# echo.net
KiCad netlist of a schematic drawn in EAGLE
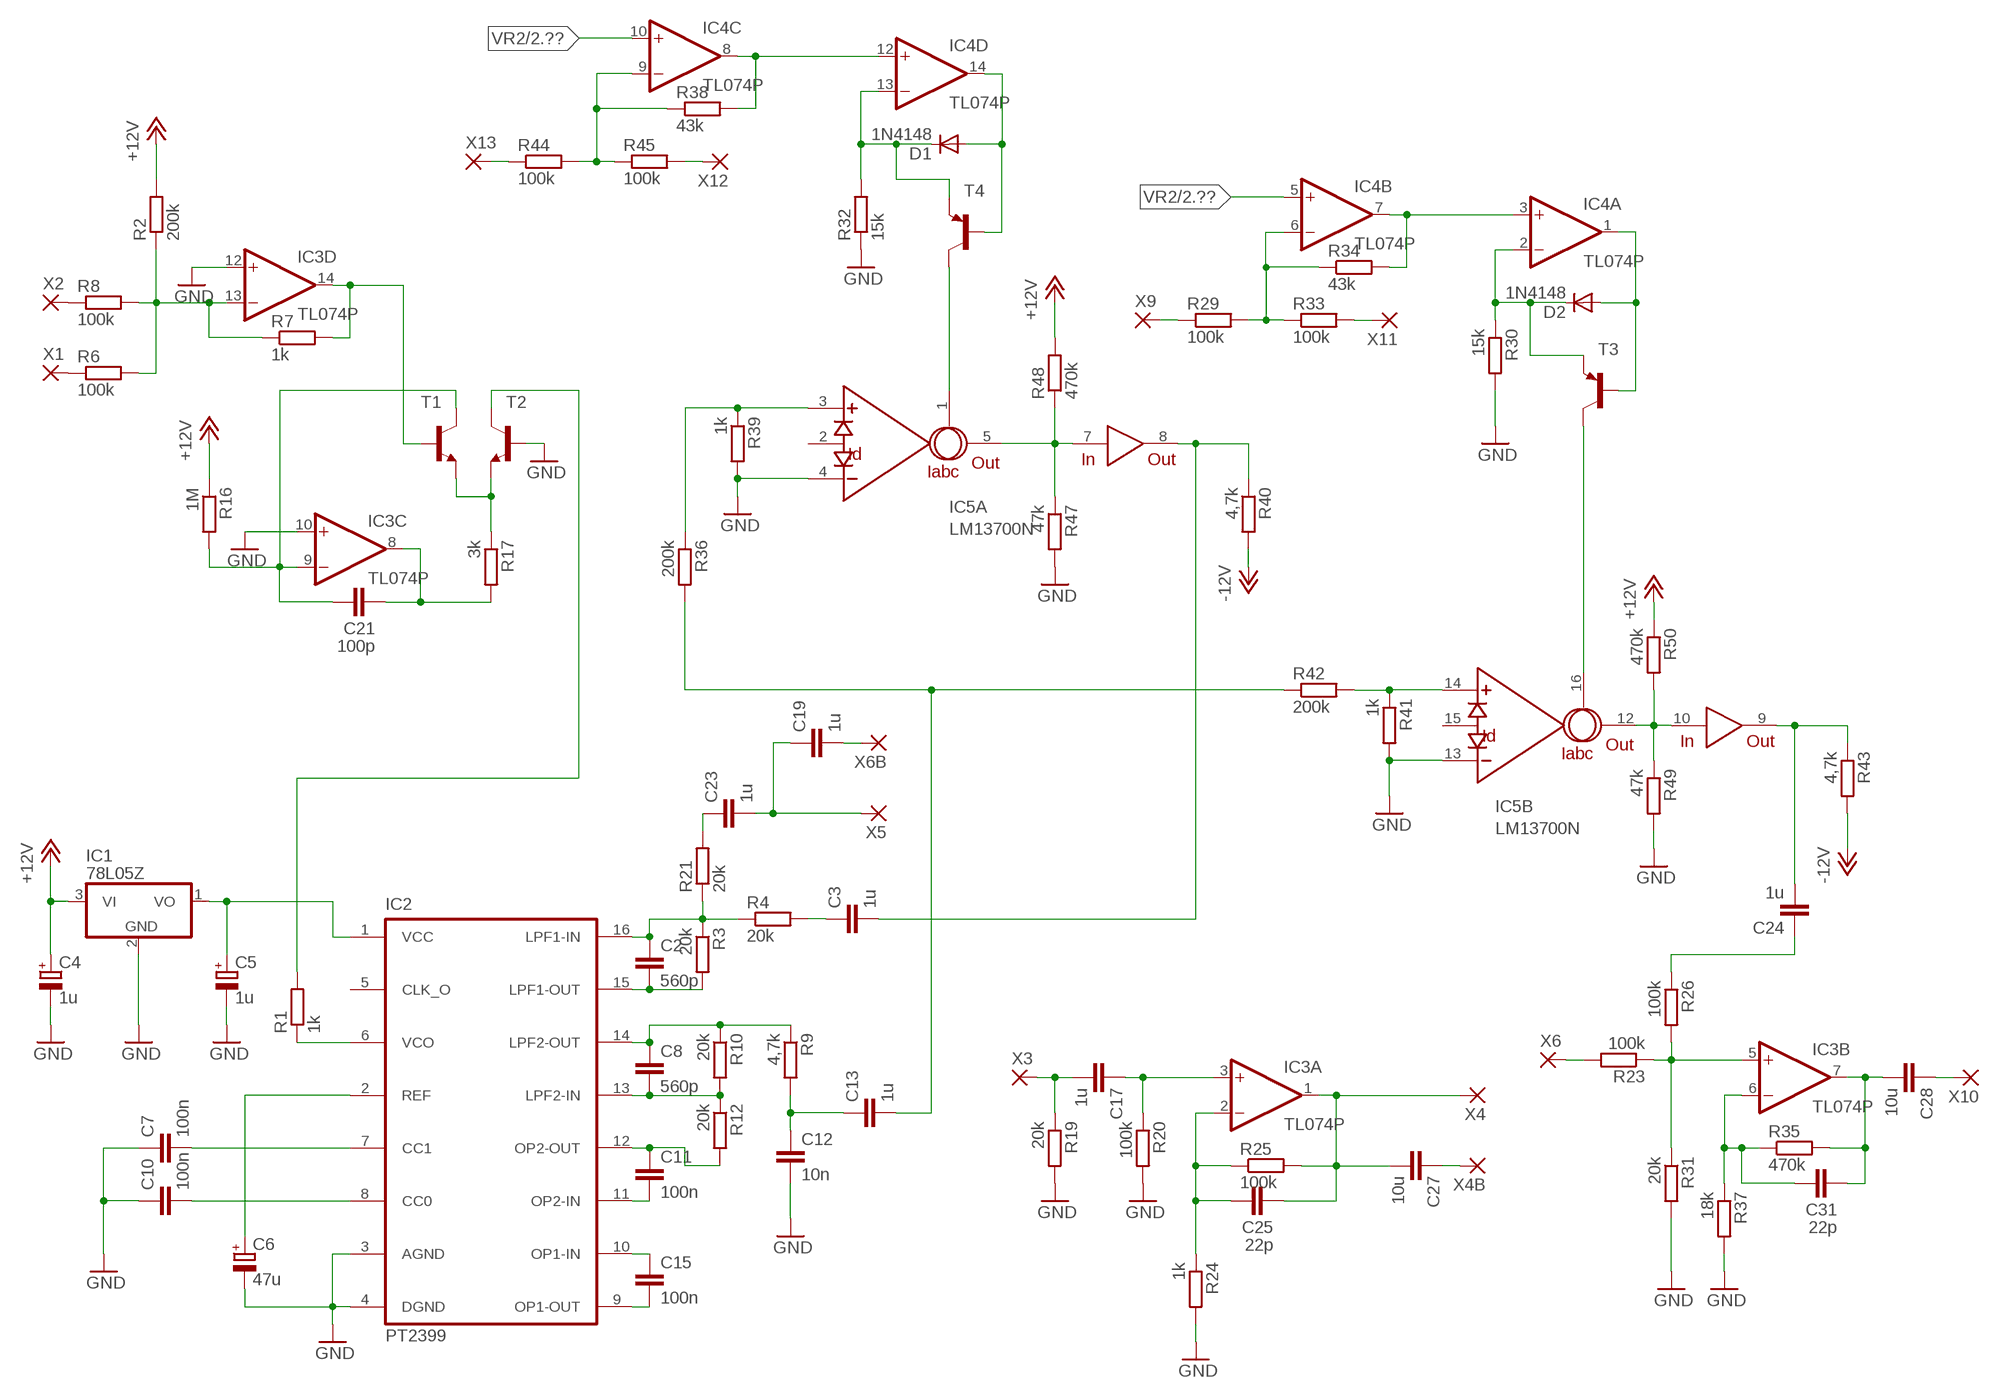
[diagram p0: schematic, sheet 1]
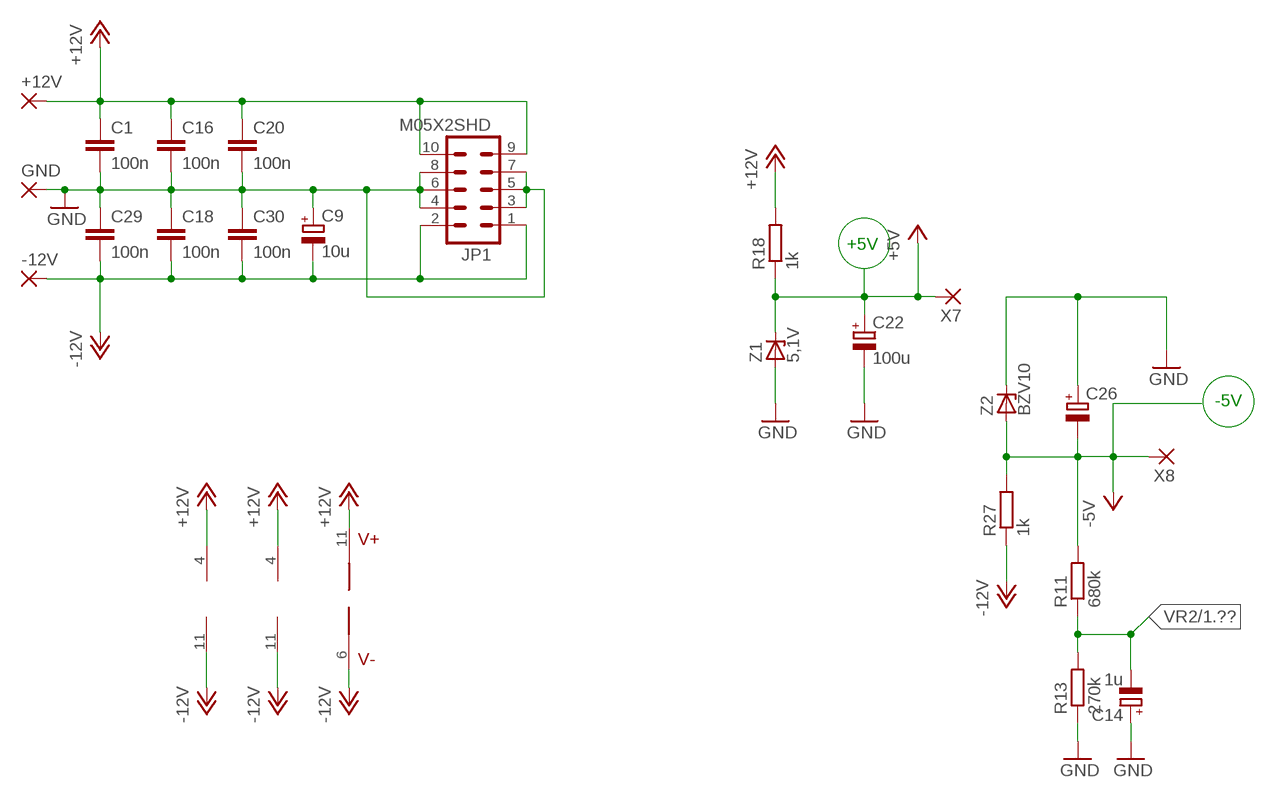
[diagram p1: schematic, sheet 2]

(export (version "E")
  (design (tool "Eeschema 10.0.6"))
  (components
    (comp (ref "+12V")
      (value "2,54/1,0")
      (footprint "eagle-import:2,54_1,0")
      (libsource (lib "eagle-import") (part "2,54/1,0"))
    )
    (comp (ref "-12V")
      (value "2,54/1,0")
      (footprint "eagle-import:2,54_1,0")
      (libsource (lib "eagle-import") (part "2,54/1,0"))
    )
    (comp (ref "C1")
      (value "100n")
      (footprint "eagle-import:C025-025X050")
      (libsource (lib "eagle-import") (part "C-EU025-025X050"))
    )
    (comp (ref "C9")
      (value "10u")
      (footprint "eagle-import:E2-5")
      (libsource (lib "eagle-import") (part "CPOL-EUE2-5"))
    )
    (comp (ref "C14")
      (value "1u")
      (footprint "eagle-import:E2-5")
      (libsource (lib "eagle-import") (part "CPOL-EUE2-5"))
    )
    (comp (ref "C16")
      (value "100n")
      (footprint "eagle-import:C025-025X050")
      (libsource (lib "eagle-import") (part "C-EU025-025X050"))
    )
    (comp (ref "C18")
      (value "100n")
      (footprint "eagle-import:C025-025X050")
      (libsource (lib "eagle-import") (part "C-EU025-025X050"))
    )
    (comp (ref "C20")
      (value "100n")
      (footprint "eagle-import:C025-025X050")
      (libsource (lib "eagle-import") (part "C-EU025-025X050"))
    )
    (comp (ref "C22")
      (value "100u")
      (footprint "eagle-import:E2-5")
      (libsource (lib "eagle-import") (part "CPOL-EUE2-5"))
    )
    (comp (ref "C26")
      (value "CPOL-EUE2-5")
      (footprint "eagle-import:E2-5")
      (libsource (lib "eagle-import") (part "CPOL-EUE2-5"))
    )
    (comp (ref "C29")
      (value "100n")
      (footprint "eagle-import:C025-025X050")
      (libsource (lib "eagle-import") (part "C-EU025-025X050"))
    )
    (comp (ref "C30")
      (value "100n")
      (footprint "eagle-import:C025-025X050")
      (libsource (lib "eagle-import") (part "C-EU025-025X050"))
    )
    (comp (ref "GND")
      (value "2,54/1,0")
      (footprint "eagle-import:2,54_1,0")
      (libsource (lib "eagle-import") (part "2,54/1,0"))
    )
    (comp (ref "IC3")
      (value "TL074P")
      (footprint "eagle-import:DIL14")
      (libsource (lib "eagle-import") (part "TL074P"))
    )
    (comp (ref "IC4")
      (value "TL074P")
      (footprint "eagle-import:DIL14")
      (libsource (lib "eagle-import") (part "TL074P"))
    )
    (comp (ref "IC5")
      (value "LM13700N")
      (footprint "eagle-import:DIL16")
      (libsource (lib "eagle-import") (part "LM13700N"))
    )
    (comp (ref "JP1")
      (value "M05X2SHD")
      (footprint "eagle-import:2X5-SHROUDED")
      (libsource (lib "eagle-import") (part "M05X2SHD"))
    )
    (comp (ref "R11")
      (value "680k")
      (footprint "eagle-import:0309V")
      (libsource (lib "eagle-import") (part "R-EU_0309/V"))
    )
    (comp (ref "R13")
      (value "270k")
      (footprint "eagle-import:0309V")
      (libsource (lib "eagle-import") (part "R-EU_0309/V"))
    )
    (comp (ref "R18")
      (value "1k")
      (footprint "eagle-import:0309V")
      (libsource (lib "eagle-import") (part "R-EU_0309/V"))
    )
    (comp (ref "R27")
      (value "1k")
      (footprint "eagle-import:0309V")
      (libsource (lib "eagle-import") (part "R-EU_0309/V"))
    )
    (comp (ref "X7")
      (value "2,54/1,0")
      (footprint "eagle-import:2,54_1,0")
      (libsource (lib "eagle-import") (part "2,54/1,0"))
    )
    (comp (ref "X8")
      (value "2,54/1,0")
      (footprint "eagle-import:2,54_1,0")
      (libsource (lib "eagle-import") (part "2,54/1,0"))
    )
    (comp (ref "Z1")
      (value "5,1V")
      (footprint "eagle-import:DO34Z7")
      (libsource (lib "eagle-import") (part "BZV10"))
    )
    (comp (ref "Z2")
      (value "BZV10")
      (footprint "eagle-import:DO34Z7")
      (libsource (lib "eagle-import") (part "BZV10"))
    )
    (comp (ref "C2")
      (value "560p")
      (footprint "eagle-import:C050-035X075")
      (libsource (lib "eagle-import") (part "C-EU050-035X075"))
    )
    (comp (ref "C3")
      (value "1u")
      (footprint "eagle-import:C050-055X075")
      (libsource (lib "eagle-import") (part "C-EU050-055X075"))
    )
    (comp (ref "C4")
      (value "1u")
      (footprint "eagle-import:E2-5")
      (libsource (lib "eagle-import") (part "CPOL-EUE2-5"))
    )
    (comp (ref "C5")
      (value "1u")
      (footprint "eagle-import:E2-5")
      (libsource (lib "eagle-import") (part "CPOL-EUE2-5"))
    )
    (comp (ref "C6")
      (value "47u")
      (footprint "eagle-import:E2-5")
      (libsource (lib "eagle-import") (part "CPOL-EUE2-5"))
    )
    (comp (ref "C7")
      (value "100n")
      (footprint "eagle-import:C050-035X075")
      (libsource (lib "eagle-import") (part "C-EU050-035X075"))
    )
    (comp (ref "C8")
      (value "560p")
      (footprint "eagle-import:C050-035X075")
      (libsource (lib "eagle-import") (part "C-EU050-035X075"))
    )
    (comp (ref "C10")
      (value "100n")
      (footprint "eagle-import:C050-035X075")
      (libsource (lib "eagle-import") (part "C-EU050-035X075"))
    )
    (comp (ref "C11")
      (value "100n")
      (footprint "eagle-import:C050-035X075")
      (libsource (lib "eagle-import") (part "C-EU050-035X075"))
    )
    (comp (ref "C12")
      (value "10n")
      (footprint "eagle-import:C050-035X075")
      (libsource (lib "eagle-import") (part "C-EU050-035X075"))
    )
    (comp (ref "C13")
      (value "1u")
      (footprint "eagle-import:C050-055X075")
      (libsource (lib "eagle-import") (part "C-EU050-055X075"))
    )
    (comp (ref "C15")
      (value "100n")
      (footprint "eagle-import:C050-035X075")
      (libsource (lib "eagle-import") (part "C-EU050-035X075"))
    )
    (comp (ref "C17")
      (value "1u")
      (footprint "eagle-import:C050-055X075")
      (libsource (lib "eagle-import") (part "C-EU050-055X075"))
    )
    (comp (ref "C19")
      (value "1u")
      (footprint "eagle-import:C050-055X075")
      (libsource (lib "eagle-import") (part "C-EU050-055X075"))
    )
    (comp (ref "C21")
      (value "100p")
      (footprint "eagle-import:C025-025X050")
      (libsource (lib "eagle-import") (part "C-EU025-025X050"))
    )
    (comp (ref "C23")
      (value "1u")
      (footprint "eagle-import:C050-055X075")
      (libsource (lib "eagle-import") (part "C-EU050-055X075"))
    )
    (comp (ref "C24")
      (value "1u")
      (footprint "eagle-import:C050-055X075")
      (libsource (lib "eagle-import") (part "C-EU050-055X075"))
    )
    (comp (ref "C25")
      (value "22p")
      (footprint "eagle-import:C025-025X050")
      (libsource (lib "eagle-import") (part "C-EU025-025X050"))
    )
    (comp (ref "C27")
      (value "10u")
      (footprint "eagle-import:C050-055X075")
      (libsource (lib "eagle-import") (part "C-EU050-055X075"))
    )
    (comp (ref "C28")
      (value "10u")
      (footprint "eagle-import:C050-055X075")
      (libsource (lib "eagle-import") (part "C-EU050-055X075"))
    )
    (comp (ref "C31")
      (value "22p")
      (footprint "eagle-import:C025-025X050")
      (libsource (lib "eagle-import") (part "C-EU025-025X050"))
    )
    (comp (ref "D1")
      (value "1N4148")
      (footprint "eagle-import:DO35-7")
      (libsource (lib "eagle-import") (part "1N4148DO35-7"))
    )
    (comp (ref "D2")
      (value "1N4148")
      (footprint "eagle-import:DO35-7")
      (libsource (lib "eagle-import") (part "1N4148DO35-7"))
    )
    (comp (ref "IC1")
      (value "78L05Z")
      (footprint "eagle-import:TO92")
      (libsource (lib "eagle-import") (part "78ZL05"))
    )
    (comp (ref "IC2")
      (value "PT2399")
      (footprint "eagle-import:DIL16")
      (libsource (lib "eagle-import") (part "PT2399"))
    )
    (comp (ref "R1")
      (value "1k")
      (footprint "eagle-import:0309V")
      (libsource (lib "eagle-import") (part "R-EU_0309/V"))
    )
    (comp (ref "R2")
      (value "200k")
      (footprint "eagle-import:0309V")
      (libsource (lib "eagle-import") (part "R-EU_0309/V"))
    )
    (comp (ref "R3")
      (value "20k")
      (footprint "eagle-import:0309V")
      (libsource (lib "eagle-import") (part "R-EU_0309/V"))
    )
    (comp (ref "R4")
      (value "20k")
      (footprint "eagle-import:0309V")
      (libsource (lib "eagle-import") (part "R-EU_0309/V"))
    )
    (comp (ref "R6")
      (value "100k")
      (footprint "eagle-import:0309V")
      (libsource (lib "eagle-import") (part "R-EU_0309/V"))
    )
    (comp (ref "R7")
      (value "1k")
      (footprint "eagle-import:0309V")
      (libsource (lib "eagle-import") (part "R-EU_0309/V"))
    )
    (comp (ref "R8")
      (value "100k")
      (footprint "eagle-import:0309V")
      (libsource (lib "eagle-import") (part "R-EU_0309/V"))
    )
    (comp (ref "R9")
      (value "4,7k")
      (footprint "eagle-import:0309V")
      (libsource (lib "eagle-import") (part "R-EU_0309/V"))
    )
    (comp (ref "R10")
      (value "20k")
      (footprint "eagle-import:0309V")
      (libsource (lib "eagle-import") (part "R-EU_0309/V"))
    )
    (comp (ref "R12")
      (value "20k")
      (footprint "eagle-import:0309V")
      (libsource (lib "eagle-import") (part "R-EU_0309/V"))
    )
    (comp (ref "R16")
      (value "1M")
      (footprint "eagle-import:0309V")
      (libsource (lib "eagle-import") (part "R-EU_0309/V"))
    )
    (comp (ref "R17")
      (value "3k")
      (footprint "eagle-import:0309V")
      (libsource (lib "eagle-import") (part "R-EU_0309/V"))
    )
    (comp (ref "R19")
      (value "20k")
      (footprint "eagle-import:0309V")
      (libsource (lib "eagle-import") (part "R-EU_0309/V"))
    )
    (comp (ref "R20")
      (value "100k")
      (footprint "eagle-import:0309V")
      (libsource (lib "eagle-import") (part "R-EU_0309/V"))
    )
    (comp (ref "R21")
      (value "20k")
      (footprint "eagle-import:0309V")
      (libsource (lib "eagle-import") (part "R-EU_0309/V"))
    )
    (comp (ref "R23")
      (value "100k")
      (footprint "eagle-import:0309V")
      (libsource (lib "eagle-import") (part "R-EU_0309/V"))
    )
    (comp (ref "R24")
      (value "1k")
      (footprint "eagle-import:0309V")
      (libsource (lib "eagle-import") (part "R-EU_0309/V"))
    )
    (comp (ref "R25")
      (value "100k")
      (footprint "eagle-import:0309V")
      (libsource (lib "eagle-import") (part "R-EU_0309/V"))
    )
    (comp (ref "R26")
      (value "100k")
      (footprint "eagle-import:0309V")
      (libsource (lib "eagle-import") (part "R-EU_0309/V"))
    )
    (comp (ref "R29")
      (value "100k")
      (footprint "eagle-import:0309V")
      (libsource (lib "eagle-import") (part "R-EU_0309/V"))
    )
    (comp (ref "R30")
      (value "15k")
      (footprint "eagle-import:0309V")
      (libsource (lib "eagle-import") (part "R-EU_0309/V"))
    )
    (comp (ref "R31")
      (value "20k")
      (footprint "eagle-import:0309V")
      (libsource (lib "eagle-import") (part "R-EU_0309/V"))
    )
    (comp (ref "R32")
      (value "15k")
      (footprint "eagle-import:0309V")
      (libsource (lib "eagle-import") (part "R-EU_0309/V"))
    )
    (comp (ref "R33")
      (value "100k")
      (footprint "eagle-import:0309V")
      (libsource (lib "eagle-import") (part "R-EU_0309/V"))
    )
    (comp (ref "R34")
      (value "43k")
      (footprint "eagle-import:0309V")
      (libsource (lib "eagle-import") (part "R-EU_0309/V"))
    )
    (comp (ref "R35")
      (value "470k")
      (footprint "eagle-import:0309V")
      (libsource (lib "eagle-import") (part "R-EU_0309/V"))
    )
    (comp (ref "R36")
      (value "200k")
      (footprint "eagle-import:0309V")
      (libsource (lib "eagle-import") (part "R-EU_0309/V"))
    )
    (comp (ref "R37")
      (value "18k")
      (footprint "eagle-import:0309V")
      (libsource (lib "eagle-import") (part "R-EU_0309/V"))
    )
    (comp (ref "R38")
      (value "43k")
      (footprint "eagle-import:0309V")
      (libsource (lib "eagle-import") (part "R-EU_0309/V"))
    )
    (comp (ref "R39")
      (value "1k")
      (footprint "eagle-import:0309V")
      (libsource (lib "eagle-import") (part "R-EU_0309/V"))
    )
    (comp (ref "R40")
      (value "4,7k")
      (footprint "eagle-import:0309V")
      (libsource (lib "eagle-import") (part "R-EU_0309/V"))
    )
    (comp (ref "R41")
      (value "1k")
      (footprint "eagle-import:0309V")
      (libsource (lib "eagle-import") (part "R-EU_0309/V"))
    )
    (comp (ref "R42")
      (value "200k")
      (footprint "eagle-import:0309V")
      (libsource (lib "eagle-import") (part "R-EU_0309/V"))
    )
    (comp (ref "R43")
      (value "4,7k")
      (footprint "eagle-import:0309V")
      (libsource (lib "eagle-import") (part "R-EU_0309/V"))
    )
    (comp (ref "R44")
      (value "100k")
      (footprint "eagle-import:0309V")
      (libsource (lib "eagle-import") (part "R-EU_0309/V"))
    )
    (comp (ref "R45")
      (value "100k")
      (footprint "eagle-import:0309V")
      (libsource (lib "eagle-import") (part "R-EU_0309/V"))
    )
    (comp (ref "R47")
      (value "47k")
      (footprint "eagle-import:0309V")
      (libsource (lib "eagle-import") (part "R-EU_0309/V"))
    )
    (comp (ref "R48")
      (value "470k")
      (footprint "eagle-import:0309V")
      (libsource (lib "eagle-import") (part "R-EU_0309/V"))
    )
    (comp (ref "R49")
      (value "47k")
      (footprint "eagle-import:0309V")
      (libsource (lib "eagle-import") (part "R-EU_0309/V"))
    )
    (comp (ref "R50")
      (value "470k")
      (footprint "eagle-import:0309V")
      (libsource (lib "eagle-import") (part "R-EU_0309/V"))
    )
    (comp (ref "T1")
      (value "2N3904-NPN-TO92-EBC")
      (footprint "eagle-import:TO92-EBC")
      (libsource (lib "eagle-import") (part "-NPN-TO92-EBC2N3904"))
    )
    (comp (ref "T2")
      (value "2N3904-NPN-TO92-EBC")
      (footprint "eagle-import:TO92-EBC")
      (libsource (lib "eagle-import") (part "-NPN-TO92-EBC2N3904"))
    )
    (comp (ref "T3")
      (value "2N3906-PNP-TO92-EBC")
      (footprint "eagle-import:TO92-EBC")
      (libsource (lib "eagle-import") (part "-PNP-TO92-EBC2N3906"))
    )
    (comp (ref "T4")
      (value "2N3906-PNP-TO92-EBC")
      (footprint "eagle-import:TO92-EBC")
      (libsource (lib "eagle-import") (part "-PNP-TO92-EBC2N3906"))
    )
    (comp (ref "X1")
      (value "2,54/1,0")
      (footprint "eagle-import:2,54_1,0")
      (libsource (lib "eagle-import") (part "2,54/1,0"))
    )
    (comp (ref "X2")
      (value "2,54/1,0")
      (footprint "eagle-import:2,54_1,0")
      (libsource (lib "eagle-import") (part "2,54/1,0"))
    )
    (comp (ref "X3")
      (value "2,54/1,0")
      (footprint "eagle-import:2,54_1,0")
      (libsource (lib "eagle-import") (part "2,54/1,0"))
    )
    (comp (ref "X4")
      (value "2,54/1,0")
      (footprint "eagle-import:2,54_1,0")
      (libsource (lib "eagle-import") (part "2,54/1,0"))
    )
    (comp (ref "X4B")
      (value "2,54/1,0")
      (footprint "eagle-import:2,54_1,0")
      (libsource (lib "eagle-import") (part "2,54/1,0"))
    )
    (comp (ref "X5")
      (value "2,54/1,0")
      (footprint "eagle-import:2,54_1,0")
      (libsource (lib "eagle-import") (part "2,54/1,0"))
    )
    (comp (ref "X6")
      (value "2,54/1,0")
      (footprint "eagle-import:2,54_1,0")
      (libsource (lib "eagle-import") (part "2,54/1,0"))
    )
    (comp (ref "X6B")
      (value "2,54/1,0")
      (footprint "eagle-import:2,54_1,0")
      (libsource (lib "eagle-import") (part "2,54/1,0"))
    )
    (comp (ref "X9")
      (value "2,54/1,0")
      (footprint "eagle-import:2,54_1,0")
      (libsource (lib "eagle-import") (part "2,54/1,0"))
    )
    (comp (ref "X10")
      (value "2,54/1,0")
      (footprint "eagle-import:2,54_1,0")
      (libsource (lib "eagle-import") (part "2,54/1,0"))
    )
    (comp (ref "X11")
      (value "2,54/1,0")
      (footprint "eagle-import:2,54_1,0")
      (libsource (lib "eagle-import") (part "2,54/1,0"))
    )
    (comp (ref "X12")
      (value "2,54/1,0")
      (footprint "eagle-import:2,54_1,0")
      (libsource (lib "eagle-import") (part "2,54/1,0"))
    )
    (comp (ref "X13")
      (value "2,54/1,0")
      (footprint "eagle-import:2,54_1,0")
      (libsource (lib "eagle-import") (part "2,54/1,0"))
    )
  )
  (nets
    (net (code "1") (name "+5V") (class "Default")
      (node (ref "C22") (pin "+") (pinfunction "+_+") (pintype "passive"))
      (node (ref "R18") (pin "1") (pinfunction "1_1") (pintype "passive"))
      (node (ref "X7") (pin "1") (pinfunction "P_1") (pintype "passive"))
      (node (ref "Z1") (pin "C") (pinfunction "C_C") (pintype "passive"))
    )
    (net (code "2") (name "+12V") (class "Default")
      (node (ref "+12V") (pin "1") (pinfunction "P_1") (pintype "passive"))
      (node (ref "C1") (pin "1") (pinfunction "1_1") (pintype "passive"))
      (node (ref "C16") (pin "1") (pinfunction "1_1") (pintype "passive"))
      (node (ref "C20") (pin "1") (pinfunction "1_1") (pintype "passive"))
      (node (ref "C4") (pin "+") (pinfunction "+_+") (pintype "passive"))
      (node (ref "IC1") (pin "3") (pinfunction "VI_3") (pintype "input"))
      (node (ref "IC3") (pin "4") (pinfunction "V+_4") (pintype "power_in"))
      (node (ref "IC4") (pin "4") (pinfunction "V+_4") (pintype "power_in"))
      (node (ref "IC5") (pin "11") (pinfunction "V+_11") (pintype "bidirectional"))
      (node (ref "JP1") (pin "10") (pinfunction "10_10") (pintype "passive"))
      (node (ref "JP1") (pin "9") (pinfunction "9_9") (pintype "passive"))
      (node (ref "R16") (pin "1") (pinfunction "1_1") (pintype "passive"))
      (node (ref "R18") (pin "2") (pinfunction "2_2") (pintype "passive"))
      (node (ref "R2") (pin "2") (pinfunction "2_2") (pintype "passive"))
      (node (ref "R48") (pin "2") (pinfunction "2_2") (pintype "passive"))
      (node (ref "R50") (pin "1") (pinfunction "1_1") (pintype "passive"))
    )
    (net (code "3") (name "-5V") (class "Default")
      (node (ref "C26") (pin "-") (pinfunction "-_-") (pintype "passive"))
      (node (ref "R11") (pin "2") (pinfunction "2_2") (pintype "passive"))
      (node (ref "R27") (pin "2") (pinfunction "2_2") (pintype "passive"))
      (node (ref "X8") (pin "1") (pinfunction "P_1") (pintype "passive"))
      (node (ref "Z2") (pin "A") (pinfunction "A_A") (pintype "passive"))
    )
    (net (code "4") (name "-12V") (class "Default")
      (node (ref "-12V") (pin "1") (pinfunction "P_1") (pintype "passive"))
      (node (ref "C18") (pin "2") (pinfunction "2_2") (pintype "passive"))
      (node (ref "C29") (pin "2") (pinfunction "2_2") (pintype "passive"))
      (node (ref "C30") (pin "2") (pinfunction "2_2") (pintype "passive"))
      (node (ref "C9") (pin "-") (pinfunction "-_-") (pintype "passive"))
      (node (ref "IC3") (pin "11") (pinfunction "V-_11") (pintype "power_in"))
      (node (ref "IC4") (pin "11") (pinfunction "V-_11") (pintype "power_in"))
      (node (ref "IC5") (pin "6") (pinfunction "V-_6") (pintype "bidirectional"))
      (node (ref "JP1") (pin "1") (pinfunction "1_1") (pintype "passive"))
      (node (ref "JP1") (pin "2") (pinfunction "2_2") (pintype "passive"))
      (node (ref "R27") (pin "1") (pinfunction "1_1") (pintype "passive"))
      (node (ref "R40") (pin "2") (pinfunction "2_2") (pintype "passive"))
      (node (ref "R43") (pin "2") (pinfunction "2_2") (pintype "passive"))
    )
    (net (code "5") (name "GND") (class "Default")
      (node (ref "C1") (pin "2") (pinfunction "2_2") (pintype "passive"))
      (node (ref "C10") (pin "1") (pinfunction "1_1") (pintype "passive"))
      (node (ref "C12") (pin "2") (pinfunction "2_2") (pintype "passive"))
      (node (ref "C14") (pin "+") (pinfunction "+_+") (pintype "passive"))
      (node (ref "C16") (pin "2") (pinfunction "2_2") (pintype "passive"))
      (node (ref "C18") (pin "1") (pinfunction "1_1") (pintype "passive"))
      (node (ref "C20") (pin "2") (pinfunction "2_2") (pintype "passive"))
      (node (ref "C22") (pin "-") (pinfunction "-_-") (pintype "passive"))
      (node (ref "C26") (pin "+") (pinfunction "+_+") (pintype "passive"))
      (node (ref "C29") (pin "1") (pinfunction "1_1") (pintype "passive"))
      (node (ref "C30") (pin "1") (pinfunction "1_1") (pintype "passive"))
      (node (ref "C4") (pin "-") (pinfunction "-_-") (pintype "passive"))
      (node (ref "C5") (pin "-") (pinfunction "-_-") (pintype "passive"))
      (node (ref "C6") (pin "-") (pinfunction "-_-") (pintype "passive"))
      (node (ref "C7") (pin "1") (pinfunction "1_1") (pintype "passive"))
      (node (ref "C9") (pin "+") (pinfunction "+_+") (pintype "passive"))
      (node (ref "GND") (pin "1") (pinfunction "P_1") (pintype "passive"))
      (node (ref "IC1") (pin "2") (pinfunction "GND_2") (pintype "passive"))
      (node (ref "IC2") (pin "3") (pinfunction "AGND_3") (pintype "power_in"))
      (node (ref "IC2") (pin "4") (pinfunction "DGND_4") (pintype "power_in"))
      (node (ref "IC3") (pin "10") (pinfunction "+IN_10") (pintype "input"))
      (node (ref "IC3") (pin "12") (pinfunction "+IN_12") (pintype "input"))
      (node (ref "IC5") (pin "13") (pinfunction "-IN_13") (pintype "bidirectional"))
      (node (ref "IC5") (pin "4") (pinfunction "-IN_4") (pintype "bidirectional"))
      (node (ref "JP1") (pin "3") (pinfunction "3_3") (pintype "passive"))
      (node (ref "JP1") (pin "4") (pinfunction "4_4") (pintype "passive"))
      (node (ref "JP1") (pin "5") (pinfunction "5_5") (pintype "passive"))
      (node (ref "JP1") (pin "6") (pinfunction "6_6") (pintype "passive"))
      (node (ref "JP1") (pin "7") (pinfunction "7_7") (pintype "passive"))
      (node (ref "JP1") (pin "8") (pinfunction "8_8") (pintype "passive"))
      (node (ref "R13") (pin "1") (pinfunction "1_1") (pintype "passive"))
      (node (ref "R19") (pin "2") (pinfunction "2_2") (pintype "passive"))
      (node (ref "R20") (pin "2") (pinfunction "2_2") (pintype "passive"))
      (node (ref "R24") (pin "2") (pinfunction "2_2") (pintype "passive"))
      (node (ref "R30") (pin "2") (pinfunction "2_2") (pintype "passive"))
      (node (ref "R31") (pin "2") (pinfunction "2_2") (pintype "passive"))
      (node (ref "R32") (pin "1") (pinfunction "1_1") (pintype "passive"))
      (node (ref "R37") (pin "2") (pinfunction "2_2") (pintype "passive"))
      (node (ref "R39") (pin "2") (pinfunction "2_2") (pintype "passive"))
      (node (ref "R41") (pin "2") (pinfunction "2_2") (pintype "passive"))
      (node (ref "R47") (pin "2") (pinfunction "2_2") (pintype "passive"))
      (node (ref "R49") (pin "2") (pinfunction "2_2") (pintype "passive"))
      (node (ref "T2") (pin "B") (pinfunction "B_B") (pintype "passive"))
      (node (ref "Z1") (pin "A") (pinfunction "A_A") (pintype "passive"))
      (node (ref "Z2") (pin "C") (pinfunction "C_C") (pintype "passive"))
    )
    (net (code "6") (name "Net-(C3-Pad1)") (class "Default")
      (node (ref "C3") (pin "1") (pinfunction "1_1") (pintype "passive"))
      (node (ref "R4") (pin "2") (pinfunction "2_2") (pintype "passive"))
    )
    (net (code "7") (name "Net-(C12-Pad1)") (class "Default")
      (node (ref "C12") (pin "1") (pinfunction "1_1") (pintype "passive"))
      (node (ref "C13") (pin "1") (pinfunction "1_1") (pintype "passive"))
      (node (ref "R9") (pin "2") (pinfunction "2_2") (pintype "passive"))
    )
    (net (code "8") (name "Net-(C13-Pad2)") (class "Default")
      (node (ref "C13") (pin "2") (pinfunction "2_2") (pintype "passive"))
      (node (ref "R36") (pin "2") (pinfunction "2_2") (pintype "passive"))
      (node (ref "R42") (pin "1") (pinfunction "1_1") (pintype "passive"))
    )
    (net (code "9") (name "Net-(C23-Pad1)") (class "Default")
      (node (ref "C23") (pin "1") (pinfunction "1_1") (pintype "passive"))
      (node (ref "R21") (pin "2") (pinfunction "2_2") (pintype "passive"))
    )
    (net (code "10") (name "Net-(C24-Pad1)") (class "Default")
      (node (ref "C24") (pin "1") (pinfunction "1_1") (pintype "passive"))
      (node (ref "R26") (pin "1") (pinfunction "1_1") (pintype "passive"))
    )
    (net (code "11") (name "Net-(IC1-VO)") (class "Default")
      (node (ref "C5") (pin "+") (pinfunction "+_+") (pintype "passive"))
      (node (ref "IC1") (pin "1") (pinfunction "VO_1") (pintype "passive"))
      (node (ref "IC2") (pin "1") (pinfunction "VCC_1") (pintype "power_in"))
    )
    (net (code "12") (name "Net-(IC2-CC0)") (class "Default")
      (node (ref "C10") (pin "2") (pinfunction "2_2") (pintype "passive"))
      (node (ref "IC2") (pin "8") (pinfunction "CC0_8") (pintype "input"))
    )
    (net (code "13") (name "Net-(IC2-CC1)") (class "Default")
      (node (ref "C7") (pin "2") (pinfunction "2_2") (pintype "passive"))
      (node (ref "IC2") (pin "7") (pinfunction "CC1_7") (pintype "input"))
    )
    (net (code "14") (name "Net-(IC2-LPF1-IN)") (class "Default")
      (node (ref "C2") (pin "1") (pinfunction "1_1") (pintype "passive"))
      (node (ref "IC2") (pin "16") (pinfunction "LPF1-IN_16") (pintype "input"))
      (node (ref "R21") (pin "1") (pinfunction "1_1") (pintype "passive"))
      (node (ref "R3") (pin "1") (pinfunction "1_1") (pintype "passive"))
      (node (ref "R4") (pin "1") (pinfunction "1_1") (pintype "passive"))
    )
    (net (code "15") (name "Net-(IC2-LPF1-OUT)") (class "Default")
      (node (ref "C2") (pin "2") (pinfunction "2_2") (pintype "passive"))
      (node (ref "IC2") (pin "15") (pinfunction "LPF1-OUT_15") (pintype "output"))
      (node (ref "R3") (pin "2") (pinfunction "2_2") (pintype "passive"))
    )
    (net (code "16") (name "Net-(IC2-LPF2-IN)") (class "Default")
      (node (ref "C8") (pin "2") (pinfunction "2_2") (pintype "passive"))
      (node (ref "IC2") (pin "13") (pinfunction "LPF2-IN_13") (pintype "input"))
      (node (ref "R10") (pin "2") (pinfunction "2_2") (pintype "passive"))
      (node (ref "R12") (pin "1") (pinfunction "1_1") (pintype "passive"))
    )
    (net (code "17") (name "Net-(IC2-LPF2-OUT)") (class "Default")
      (node (ref "C8") (pin "1") (pinfunction "1_1") (pintype "passive"))
      (node (ref "IC2") (pin "14") (pinfunction "LPF2-OUT_14") (pintype "output"))
      (node (ref "R10") (pin "1") (pinfunction "1_1") (pintype "passive"))
      (node (ref "R9") (pin "1") (pinfunction "1_1") (pintype "passive"))
    )
    (net (code "18") (name "Net-(IC2-OP1-IN)") (class "Default")
      (node (ref "C15") (pin "1") (pinfunction "1_1") (pintype "passive"))
      (node (ref "IC2") (pin "10") (pinfunction "OP1-IN_10") (pintype "input"))
    )
    (net (code "19") (name "Net-(IC2-OP1-OUT)") (class "Default")
      (node (ref "C15") (pin "2") (pinfunction "2_2") (pintype "passive"))
      (node (ref "IC2") (pin "9") (pinfunction "OP1-OUT_9") (pintype "output"))
    )
    (net (code "20") (name "Net-(IC2-OP2-IN)") (class "Default")
      (node (ref "C11") (pin "2") (pinfunction "2_2") (pintype "passive"))
      (node (ref "IC2") (pin "11") (pinfunction "OP2-IN_11") (pintype "input"))
    )
    (net (code "21") (name "Net-(IC2-OP2-OUT)") (class "Default")
      (node (ref "C11") (pin "1") (pinfunction "1_1") (pintype "passive"))
      (node (ref "IC2") (pin "12") (pinfunction "OP2-OUT_12") (pintype "output"))
      (node (ref "R12") (pin "2") (pinfunction "2_2") (pintype "passive"))
    )
    (net (code "22") (name "Net-(IC2-REF)") (class "Default")
      (node (ref "C6") (pin "+") (pinfunction "+_+") (pintype "passive"))
      (node (ref "IC2") (pin "2") (pinfunction "REF_2") (pintype "input"))
    )
    (net (code "23") (name "Net-(IC2-VCO)") (class "Default")
      (node (ref "IC2") (pin "6") (pinfunction "VCO_6") (pintype "input"))
      (node (ref "R1") (pin "1") (pinfunction "1_1") (pintype "passive"))
    )
    (net (code "24") (name "Net-(IC3A-+IN)") (class "Default")
      (node (ref "C17") (pin "1") (pinfunction "1_1") (pintype "passive"))
      (node (ref "IC3") (pin "3") (pinfunction "+IN_3") (pintype "input"))
      (node (ref "R20") (pin "1") (pinfunction "1_1") (pintype "passive"))
    )
    (net (code "25") (name "Net-(IC3A--IN)") (class "Default")
      (node (ref "C25") (pin "1") (pinfunction "1_1") (pintype "passive"))
      (node (ref "IC3") (pin "2") (pinfunction "-IN_2") (pintype "input"))
      (node (ref "R24") (pin "1") (pinfunction "1_1") (pintype "passive"))
      (node (ref "R25") (pin "1") (pinfunction "1_1") (pintype "passive"))
    )
    (net (code "26") (name "Net-(IC3A-OUT)") (class "Default")
      (node (ref "C25") (pin "2") (pinfunction "2_2") (pintype "passive"))
      (node (ref "C27") (pin "2") (pinfunction "2_2") (pintype "passive"))
      (node (ref "IC3") (pin "1") (pinfunction "OUT_1") (pintype "output"))
      (node (ref "R25") (pin "2") (pinfunction "2_2") (pintype "passive"))
      (node (ref "X4") (pin "1") (pinfunction "P_1") (pintype "passive"))
    )
    (net (code "27") (name "Net-(IC3B-+IN)") (class "Default")
      (node (ref "IC3") (pin "5") (pinfunction "+IN_5") (pintype "input"))
      (node (ref "R23") (pin "1") (pinfunction "1_1") (pintype "passive"))
      (node (ref "R26") (pin "2") (pinfunction "2_2") (pintype "passive"))
      (node (ref "R31") (pin "1") (pinfunction "1_1") (pintype "passive"))
    )
    (net (code "28") (name "Net-(IC3B--IN)") (class "Default")
      (node (ref "C31") (pin "1") (pinfunction "1_1") (pintype "passive"))
      (node (ref "IC3") (pin "6") (pinfunction "-IN_6") (pintype "input"))
      (node (ref "R35") (pin "1") (pinfunction "1_1") (pintype "passive"))
      (node (ref "R37") (pin "1") (pinfunction "1_1") (pintype "passive"))
    )
    (net (code "29") (name "Net-(IC3B-OUT)") (class "Default")
      (node (ref "C28") (pin "2") (pinfunction "2_2") (pintype "passive"))
      (node (ref "C31") (pin "2") (pinfunction "2_2") (pintype "passive"))
      (node (ref "IC3") (pin "7") (pinfunction "OUT_7") (pintype "output"))
      (node (ref "R35") (pin "2") (pinfunction "2_2") (pintype "passive"))
    )
    (net (code "30") (name "Net-(IC3C--IN)") (class "Default")
      (node (ref "C21") (pin "1") (pinfunction "1_1") (pintype "passive"))
      (node (ref "IC3") (pin "9") (pinfunction "-IN_9") (pintype "input"))
      (node (ref "R16") (pin "2") (pinfunction "2_2") (pintype "passive"))
      (node (ref "T1") (pin "C") (pinfunction "C_C") (pintype "passive"))
    )
    (net (code "31") (name "Net-(IC3C-OUT)") (class "Default")
      (node (ref "C21") (pin "2") (pinfunction "2_2") (pintype "passive"))
      (node (ref "IC3") (pin "8") (pinfunction "OUT_8") (pintype "output"))
      (node (ref "R17") (pin "2") (pinfunction "2_2") (pintype "passive"))
    )
    (net (code "32") (name "Net-(IC3D--IN)") (class "Default")
      (node (ref "IC3") (pin "13") (pinfunction "-IN_13") (pintype "input"))
      (node (ref "R2") (pin "1") (pinfunction "1_1") (pintype "passive"))
      (node (ref "R6") (pin "2") (pinfunction "2_2") (pintype "passive"))
      (node (ref "R7") (pin "1") (pinfunction "1_1") (pintype "passive"))
      (node (ref "R8") (pin "2") (pinfunction "2_2") (pintype "passive"))
    )
    (net (code "33") (name "Net-(IC3D-OUT)") (class "Default")
      (node (ref "IC3") (pin "14") (pinfunction "OUT_14") (pintype "output"))
      (node (ref "R7") (pin "2") (pinfunction "2_2") (pintype "passive"))
      (node (ref "T1") (pin "B") (pinfunction "B_B") (pintype "passive"))
    )
    (net (code "34") (name "Net-(IC4A-+IN)") (class "Default")
      (node (ref "IC4") (pin "3") (pinfunction "+IN_3") (pintype "input"))
      (node (ref "IC4") (pin "7") (pinfunction "OUT_7") (pintype "output"))
      (node (ref "R34") (pin "2") (pinfunction "2_2") (pintype "passive"))
    )
    (net (code "35") (name "Net-(IC4A--IN)") (class "Default")
      (node (ref "D2") (pin "C") (pinfunction "C_C") (pintype "passive"))
      (node (ref "IC4") (pin "2") (pinfunction "-IN_2") (pintype "input"))
      (node (ref "R30") (pin "1") (pinfunction "1_1") (pintype "passive"))
      (node (ref "T3") (pin "E") (pinfunction "E_E") (pintype "passive"))
    )
    (net (code "36") (name "Net-(IC4A-OUT)") (class "Default")
      (node (ref "D2") (pin "A") (pinfunction "A_A") (pintype "passive"))
      (node (ref "IC4") (pin "1") (pinfunction "OUT_1") (pintype "output"))
      (node (ref "T3") (pin "B") (pinfunction "B_B") (pintype "passive"))
    )
    (net (code "37") (name "Net-(IC4B--IN)") (class "Default")
      (node (ref "IC4") (pin "6") (pinfunction "-IN_6") (pintype "input"))
      (node (ref "R29") (pin "2") (pinfunction "2_2") (pintype "passive"))
      (node (ref "R33") (pin "1") (pinfunction "1_1") (pintype "passive"))
      (node (ref "R34") (pin "1") (pinfunction "1_1") (pintype "passive"))
    )
    (net (code "38") (name "Net-(IC4C--IN)") (class "Default")
      (node (ref "IC4") (pin "9") (pinfunction "-IN_9") (pintype "input"))
      (node (ref "R38") (pin "1") (pinfunction "1_1") (pintype "passive"))
      (node (ref "R44") (pin "2") (pinfunction "2_2") (pintype "passive"))
      (node (ref "R45") (pin "1") (pinfunction "1_1") (pintype "passive"))
    )
    (net (code "39") (name "Net-(IC4C-OUT)") (class "Default")
      (node (ref "IC4") (pin "12") (pinfunction "+IN_12") (pintype "input"))
      (node (ref "IC4") (pin "8") (pinfunction "OUT_8") (pintype "output"))
      (node (ref "R38") (pin "2") (pinfunction "2_2") (pintype "passive"))
    )
    (net (code "40") (name "Net-(IC4D--IN)") (class "Default")
      (node (ref "D1") (pin "C") (pinfunction "C_C") (pintype "passive"))
      (node (ref "IC4") (pin "13") (pinfunction "-IN_13") (pintype "input"))
      (node (ref "R32") (pin "2") (pinfunction "2_2") (pintype "passive"))
      (node (ref "T4") (pin "E") (pinfunction "E_E") (pintype "passive"))
    )
    (net (code "41") (name "Net-(IC4D-OUT)") (class "Default")
      (node (ref "D1") (pin "A") (pinfunction "A_A") (pintype "passive"))
      (node (ref "IC4") (pin "14") (pinfunction "OUT_14") (pintype "output"))
      (node (ref "T4") (pin "B") (pinfunction "B_B") (pintype "passive"))
    )
    (net (code "42") (name "Net-(IC5A-+IN)") (class "Default")
      (node (ref "IC5") (pin "3") (pinfunction "+IN_3") (pintype "bidirectional"))
      (node (ref "R36") (pin "1") (pinfunction "1_1") (pintype "passive"))
      (node (ref "R39") (pin "1") (pinfunction "1_1") (pintype "passive"))
    )
    (net (code "43") (name "Net-(IC5A-IABC)") (class "Default")
      (node (ref "IC5") (pin "1") (pinfunction "IABC_1") (pintype "bidirectional"))
      (node (ref "T4") (pin "C") (pinfunction "C_C") (pintype "passive"))
    )
    (net (code "44") (name "Net-(IC5A-OUT)") (class "Default")
      (node (ref "IC5") (pin "5") (pinfunction "OUT_5") (pintype "bidirectional"))
      (node (ref "IC5") (pin "7") (pinfunction "IN_7") (pintype "bidirectional"))
      (node (ref "R47") (pin "1") (pinfunction "1_1") (pintype "passive"))
      (node (ref "R48") (pin "1") (pinfunction "1_1") (pintype "passive"))
    )
    (net (code "45") (name "Net-(IC5B-+IN)") (class "Default")
      (node (ref "IC5") (pin "14") (pinfunction "+IN_14") (pintype "bidirectional"))
      (node (ref "R41") (pin "1") (pinfunction "1_1") (pintype "passive"))
      (node (ref "R42") (pin "2") (pinfunction "2_2") (pintype "passive"))
    )
    (net (code "46") (name "Net-(IC5B-IABC)") (class "Default")
      (node (ref "IC5") (pin "16") (pinfunction "IABC_16") (pintype "bidirectional"))
      (node (ref "T3") (pin "C") (pinfunction "C_C") (pintype "passive"))
    )
    (net (code "47") (name "Net-(IC5B-OUT)") (class "Default")
      (node (ref "IC5") (pin "10") (pinfunction "IN_10") (pintype "bidirectional"))
      (node (ref "IC5") (pin "12") (pinfunction "OUT_12") (pintype "bidirectional"))
      (node (ref "R49") (pin "1") (pinfunction "1_1") (pintype "passive"))
      (node (ref "R50") (pin "2") (pinfunction "2_2") (pintype "passive"))
    )
    (net (code "48") (name "Net-(IC5C-OUT)") (class "Default")
      (node (ref "C3") (pin "2") (pinfunction "2_2") (pintype "passive"))
      (node (ref "IC5") (pin "8") (pinfunction "OUT_8") (pintype "bidirectional"))
      (node (ref "R40") (pin "1") (pinfunction "1_1") (pintype "passive"))
    )
    (net (code "49") (name "Net-(IC5D-OUT)") (class "Default")
      (node (ref "C24") (pin "2") (pinfunction "2_2") (pintype "passive"))
      (node (ref "IC5") (pin "9") (pinfunction "OUT_9") (pintype "bidirectional"))
      (node (ref "R43") (pin "1") (pinfunction "1_1") (pintype "passive"))
    )
    (net (code "50") (name "Net-(R1-Pad2)") (class "Default")
      (node (ref "R1") (pin "2") (pinfunction "2_2") (pintype "passive"))
      (node (ref "T2") (pin "C") (pinfunction "C_C") (pintype "passive"))
    )
    (net (code "51") (name "Net-(R17-Pad1)") (class "Default")
      (node (ref "R17") (pin "1") (pinfunction "1_1") (pintype "passive"))
      (node (ref "T1") (pin "E") (pinfunction "E_E") (pintype "passive"))
      (node (ref "T2") (pin "E") (pinfunction "E_E") (pintype "passive"))
    )
    (net (code "52") (name "Net-(X1-P)") (class "Default")
      (node (ref "R6") (pin "1") (pinfunction "1_1") (pintype "passive"))
      (node (ref "X1") (pin "1") (pinfunction "P_1") (pintype "passive"))
    )
    (net (code "53") (name "Net-(X2-P)") (class "Default")
      (node (ref "R8") (pin "1") (pinfunction "1_1") (pintype "passive"))
      (node (ref "X2") (pin "1") (pinfunction "P_1") (pintype "passive"))
    )
    (net (code "54") (name "Net-(X3-P)") (class "Default")
      (node (ref "C17") (pin "2") (pinfunction "2_2") (pintype "passive"))
      (node (ref "R19") (pin "1") (pinfunction "1_1") (pintype "passive"))
      (node (ref "X3") (pin "1") (pinfunction "P_1") (pintype "passive"))
    )
    (net (code "55") (name "Net-(X4B-P)") (class "Default")
      (node (ref "C27") (pin "1") (pinfunction "1_1") (pintype "passive"))
      (node (ref "X4B") (pin "1") (pinfunction "P_1") (pintype "passive"))
    )
    (net (code "56") (name "Net-(X5-P)") (class "Default")
      (node (ref "C19") (pin "1") (pinfunction "1_1") (pintype "passive"))
      (node (ref "C23") (pin "2") (pinfunction "2_2") (pintype "passive"))
      (node (ref "X5") (pin "1") (pinfunction "P_1") (pintype "passive"))
    )
    (net (code "57") (name "Net-(X6-P)") (class "Default")
      (node (ref "R23") (pin "2") (pinfunction "2_2") (pintype "passive"))
      (node (ref "X6") (pin "1") (pinfunction "P_1") (pintype "passive"))
    )
    (net (code "58") (name "Net-(X6B-P)") (class "Default")
      (node (ref "C19") (pin "2") (pinfunction "2_2") (pintype "passive"))
      (node (ref "X6B") (pin "1") (pinfunction "P_1") (pintype "passive"))
    )
    (net (code "59") (name "Net-(X9-P)") (class "Default")
      (node (ref "R29") (pin "1") (pinfunction "1_1") (pintype "passive"))
      (node (ref "X9") (pin "1") (pinfunction "P_1") (pintype "passive"))
    )
    (net (code "60") (name "Net-(X10-P)") (class "Default")
      (node (ref "C28") (pin "1") (pinfunction "1_1") (pintype "passive"))
      (node (ref "X10") (pin "1") (pinfunction "P_1") (pintype "passive"))
    )
    (net (code "61") (name "Net-(X11-P)") (class "Default")
      (node (ref "R33") (pin "2") (pinfunction "2_2") (pintype "passive"))
      (node (ref "X11") (pin "1") (pinfunction "P_1") (pintype "passive"))
    )
    (net (code "62") (name "Net-(X12-P)") (class "Default")
      (node (ref "R45") (pin "2") (pinfunction "2_2") (pintype "passive"))
      (node (ref "X12") (pin "1") (pinfunction "P_1") (pintype "passive"))
    )
    (net (code "63") (name "Net-(X13-P)") (class "Default")
      (node (ref "R44") (pin "1") (pinfunction "1_1") (pintype "passive"))
      (node (ref "X13") (pin "1") (pinfunction "P_1") (pintype "passive"))
    )
    (net (code "64") (name "VR2") (class "Default")
      (node (ref "C14") (pin "-") (pinfunction "-_-") (pintype "passive"))
      (node (ref "IC4") (pin "10") (pinfunction "+IN_10") (pintype "input"))
      (node (ref "IC4") (pin "5") (pinfunction "+IN_5") (pintype "input"))
      (node (ref "R11") (pin "1") (pinfunction "1_1") (pintype "passive"))
      (node (ref "R13") (pin "2") (pinfunction "2_2") (pintype "passive"))
    )
    (net (code "65") (name "unconnected-(IC2-CLK_O-Pad5)") (class "Default")
      (node (ref "IC2") (pin "5") (pinfunction "CLK_O_5") (pintype "output"))
    )
    (net (code "66") (name "unconnected-(IC5A-ID-Pad2)") (class "Default")
      (node (ref "IC5") (pin "2") (pinfunction "ID_2") (pintype "bidirectional"))
    )
    (net (code "67") (name "unconnected-(IC5B-ID-Pad15)") (class "Default")
      (node (ref "IC5") (pin "15") (pinfunction "ID_15") (pintype "bidirectional"))
    )
  )
)
